# GB-WP-D1.net
KiCad netlist of a schematic drawn in EAGLE
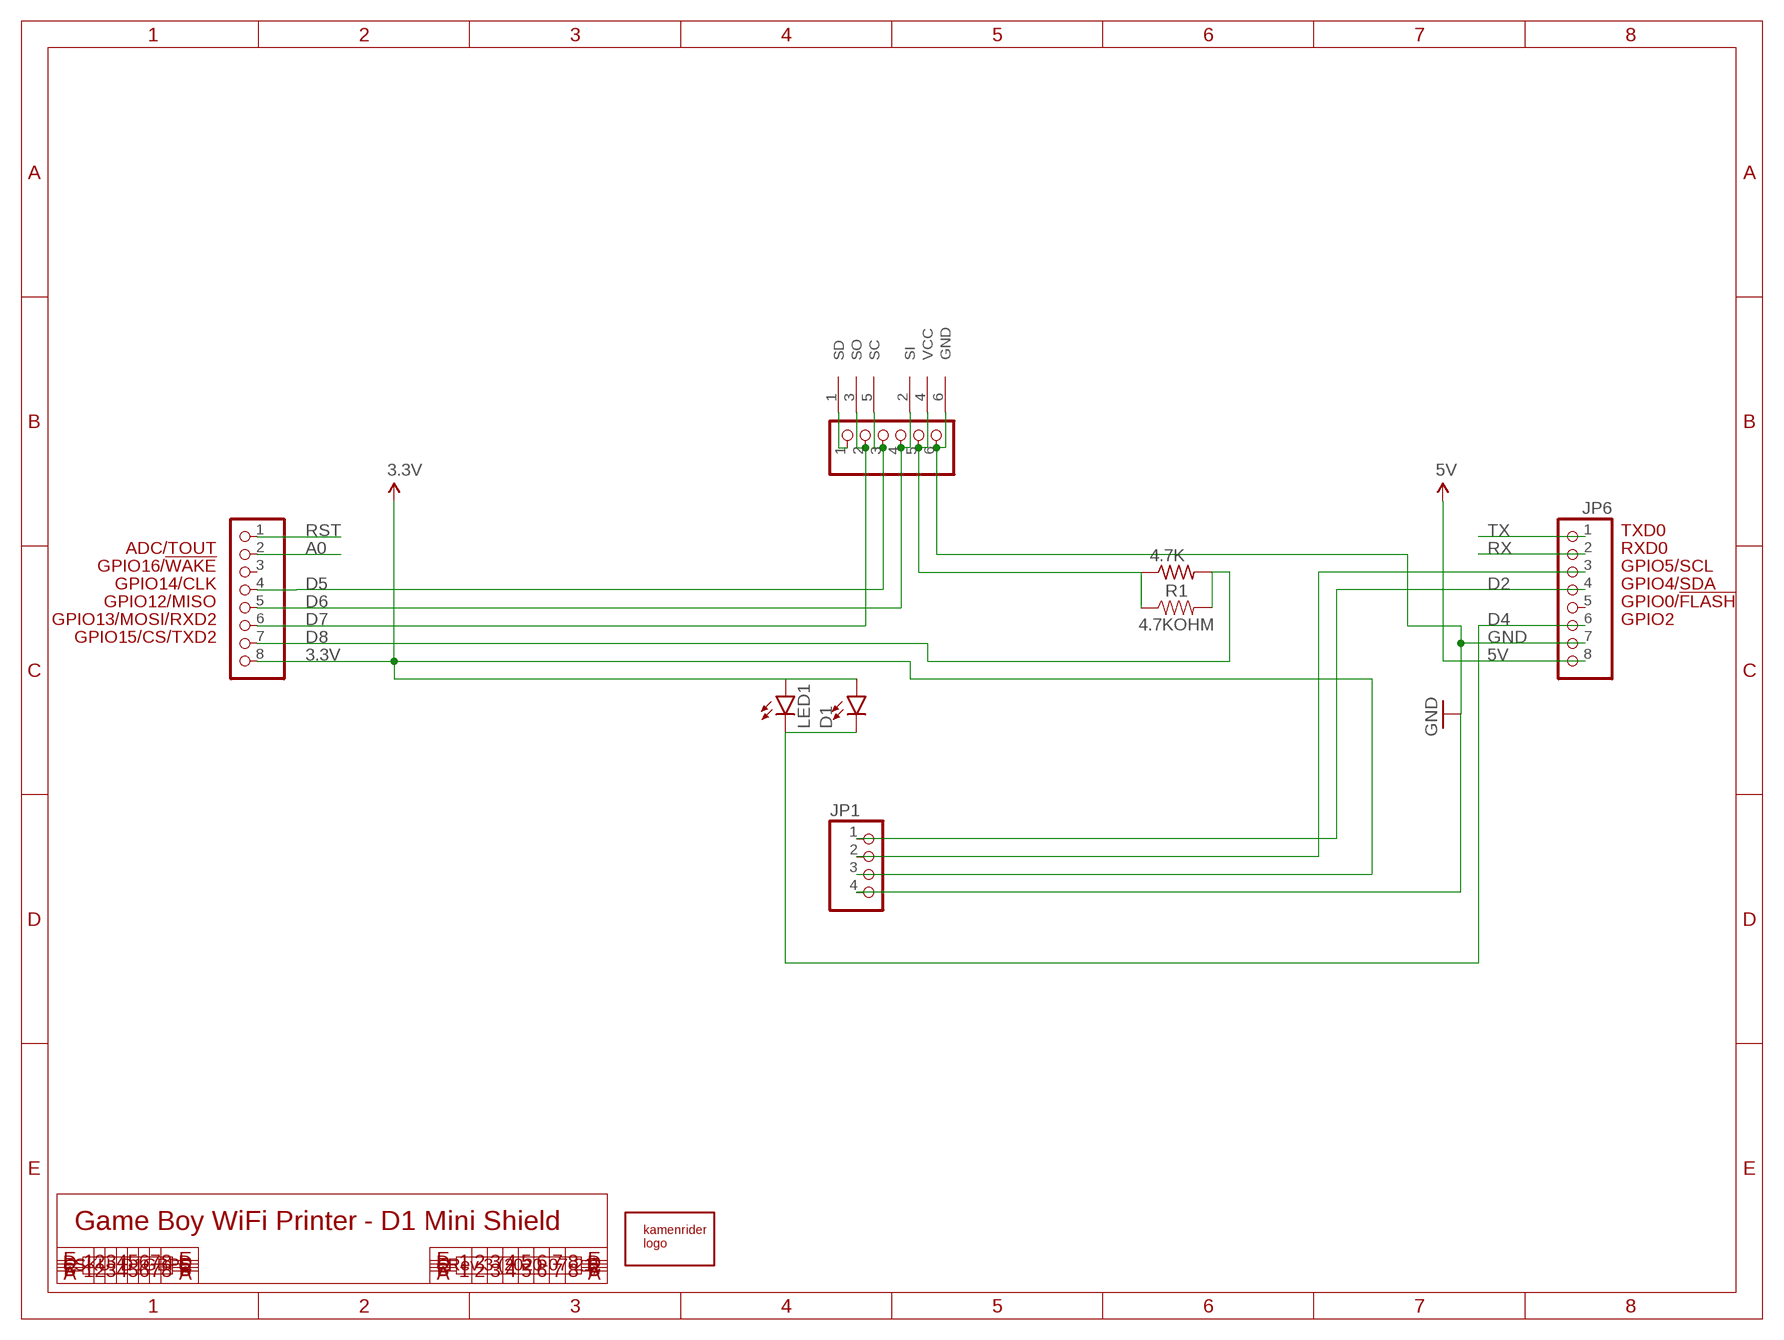
[diagram p0: schematic, sheet 1]

(export (version "E")
  (design (tool "Eeschema 10.0.6"))
  (components
    (comp (ref "4.7K")
      (value "R-US_0207/10")
      (footprint "eagle-import:0207_10")
      (libsource (lib "eagle-import") (part "R-US_0207/10"))
    )
    (comp (ref "D1")
      (value "LED1206")
      (footprint "eagle-import:LED-1206")
      (libsource (lib "eagle-import") (part "LED1206"))
    )
    (comp (ref "JP1")
      (value "PINHD-1X4/OCT")
      (footprint "eagle-import:1X04_OCT")
      (libsource (lib "eagle-import") (part "PINHD-1X4/OCT"))
    )
    (comp (ref "JP3")
      (value "PINHD-1X8/OCT")
      (footprint "eagle-import:1X08_OCT")
      (libsource (lib "eagle-import") (part "PINHD-1X8/OCT"))
    )
    (comp (ref "JP4")
      (value "PINHD-1X6/OCT")
      (footprint "eagle-import:1X06_OCT")
      (libsource (lib "eagle-import") (part "PINHD-1X6/OCT"))
    )
    (comp (ref "JP6")
      (value "PINHD-1X8/OCT")
      (footprint "eagle-import:1X08_OCT")
      (libsource (lib "eagle-import") (part "PINHD-1X8/OCT"))
    )
    (comp (ref "LED1")
      (value "LED3MM")
      (footprint "eagle-import:LED3MM")
      (libsource (lib "eagle-import") (part "led_259_LED3MM"))
    )
    (comp (ref "R1")
      (value "4.7KOHM")
      (footprint "eagle-import:1206")
      (libsource (lib "eagle-import") (part "4.7KOHM"))
    )
    (comp (ref "U$2")
      (value "GB-LINK-PADS")
      (footprint "eagle-import:GB-LINK-PCB")
      (libsource (lib "eagle-import") (part "GB-LINK-PADS"))
    )
    (comp (ref "U$3")
      (value "KAMENRIDER_LOGOV2_COLOR_OPAC")
      (footprint "eagle-import:10_6_V2")
      (libsource (lib "eagle-import") (part "KAMENRIDER_LOGOV2_COLOR_OPAC"))
    )
  )
  (nets
    (net (code "1") (name "/A0") (class "Default")
      (node (ref "JP3") (pin "2") (pinfunction "2_2") (pintype "passive"))
    )
    (net (code "2") (name "/D2") (class "Default")
      (node (ref "JP1") (pin "1") (pinfunction "1_1") (pintype "passive"))
      (node (ref "JP6") (pin "4") (pinfunction "4_4") (pintype "passive"))
    )
    (net (code "3") (name "/D4") (class "Default")
      (node (ref "D1") (pin "C") (pinfunction "C_C") (pintype "passive"))
      (node (ref "JP6") (pin "6") (pinfunction "6_6") (pintype "passive"))
      (node (ref "LED1") (pin "K") (pinfunction "C_K") (pintype "passive"))
    )
    (net (code "4") (name "/D5") (class "Default")
      (node (ref "JP3") (pin "4") (pinfunction "4_4") (pintype "passive"))
      (node (ref "JP4") (pin "3") (pinfunction "3_3") (pintype "passive"))
      (node (ref "U$2") (pin "5") (pinfunction "SC_5") (pintype "bidirectional"))
    )
    (net (code "5") (name "/D6") (class "Default")
      (node (ref "JP3") (pin "5") (pinfunction "5_5") (pintype "passive"))
      (node (ref "JP4") (pin "4") (pinfunction "4_4") (pintype "passive"))
      (node (ref "U$2") (pin "2") (pinfunction "SI_2") (pintype "bidirectional"))
    )
    (net (code "6") (name "/D7") (class "Default")
      (node (ref "JP3") (pin "6") (pinfunction "6_6") (pintype "passive"))
      (node (ref "JP4") (pin "2") (pinfunction "2_2") (pintype "passive"))
      (node (ref "U$2") (pin "3") (pinfunction "SO_3") (pintype "bidirectional"))
    )
    (net (code "7") (name "/D8") (class "Default")
      (node (ref "4.7K") (pin "2") (pinfunction "2_2") (pintype "passive"))
      (node (ref "JP3") (pin "7") (pinfunction "7_7") (pintype "passive"))
      (node (ref "R1") (pin "2") (pinfunction "2_2") (pintype "passive"))
    )
    (net (code "8") (name "/RST") (class "Default")
      (node (ref "JP3") (pin "1") (pinfunction "1_1") (pintype "passive"))
    )
    (net (code "9") (name "/RX") (class "Default")
      (node (ref "JP6") (pin "2") (pinfunction "2_2") (pintype "passive"))
    )
    (net (code "10") (name "/TX") (class "Default")
      (node (ref "JP6") (pin "1") (pinfunction "1_1") (pintype "passive"))
    )
    (net (code "11") (name "3.3V") (class "Default")
      (node (ref "D1") (pin "A") (pinfunction "A_A") (pintype "passive"))
      (node (ref "JP1") (pin "3") (pinfunction "3_3") (pintype "passive"))
      (node (ref "JP3") (pin "8") (pinfunction "8_8") (pintype "passive"))
      (node (ref "LED1") (pin "A") (pinfunction "A_A") (pintype "passive"))
    )
    (net (code "12") (name "5V") (class "Default")
      (node (ref "JP6") (pin "8") (pinfunction "8_8") (pintype "passive"))
    )
    (net (code "13") (name "GND") (class "Default")
      (node (ref "JP1") (pin "4") (pinfunction "4_4") (pintype "passive"))
      (node (ref "JP4") (pin "6") (pinfunction "6_6") (pintype "passive"))
      (node (ref "JP6") (pin "7") (pinfunction "7_7") (pintype "passive"))
      (node (ref "U$2") (pin "6") (pinfunction "GND_6") (pintype "bidirectional"))
    )
    (net (code "14") (name "Net-(JP1-Pad2)") (class "Default")
      (node (ref "JP1") (pin "2") (pinfunction "2_2") (pintype "passive"))
      (node (ref "JP6") (pin "3") (pinfunction "3_3") (pintype "passive"))
    )
    (net (code "15") (name "Net-(U$2-SD)") (class "Default")
      (node (ref "JP4") (pin "1") (pinfunction "1_1") (pintype "passive"))
      (node (ref "U$2") (pin "1") (pinfunction "SD_1") (pintype "bidirectional"))
    )
    (net (code "16") (name "Net-(U$2-VCC)") (class "Default")
      (node (ref "4.7K") (pin "1") (pinfunction "1_1") (pintype "passive"))
      (node (ref "JP4") (pin "5") (pinfunction "5_5") (pintype "passive"))
      (node (ref "R1") (pin "1") (pinfunction "1_1") (pintype "passive"))
      (node (ref "U$2") (pin "4") (pinfunction "VCC_4") (pintype "bidirectional"))
    )
    (net (code "17") (name "unconnected-(JP3-Pad3)") (class "Default")
      (node (ref "JP3") (pin "3") (pinfunction "3_3") (pintype "passive"))
    )
    (net (code "18") (name "unconnected-(JP6-Pad5)") (class "Default")
      (node (ref "JP6") (pin "5") (pinfunction "5_5") (pintype "passive"))
    )
  )
)
